# DigiIn1_1.net
KiCad netlist of a schematic drawn in EAGLE
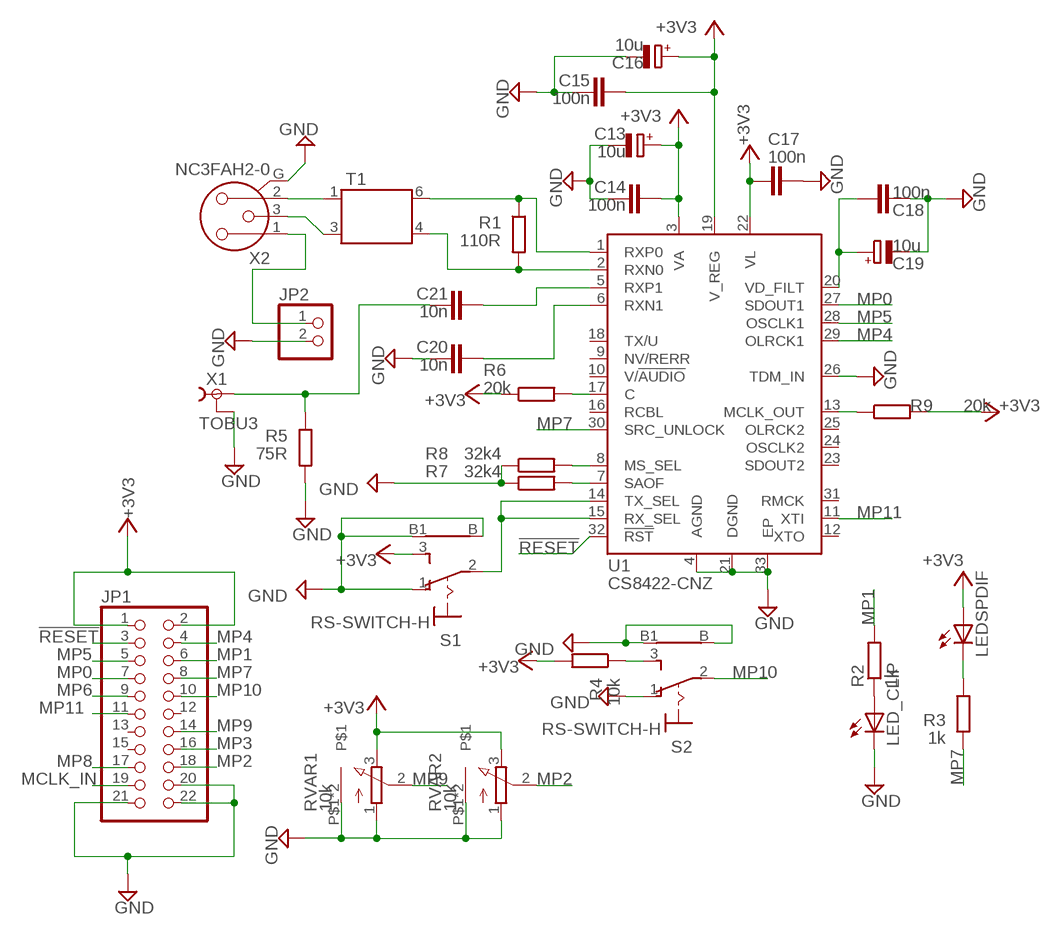
[diagram p0: schematic, sheet 1]

(export (version "E")
  (design (tool "Eeschema 10.0.6"))
  (components
    (comp (ref "C13")
      (value "10u")
      (footprint "eagle-import:E2-5")
      (libsource (lib "eagle-import") (part "CPOL-EUE2-5"))
    )
    (comp (ref "C14")
      (value "100n")
      (footprint "eagle-import:C025-024X044")
      (libsource (lib "eagle-import") (part "C-EU025-024X044"))
    )
    (comp (ref "C15")
      (value "100n")
      (footprint "eagle-import:C025-024X044")
      (libsource (lib "eagle-import") (part "C-EU025-024X044"))
    )
    (comp (ref "C16")
      (value "10u")
      (footprint "eagle-import:E2-5")
      (libsource (lib "eagle-import") (part "CPOL-EUE2-5"))
    )
    (comp (ref "C17")
      (value "100n")
      (footprint "eagle-import:C025-024X044")
      (libsource (lib "eagle-import") (part "C-EU025-024X044"))
    )
    (comp (ref "C18")
      (value "100n")
      (footprint "eagle-import:C025-024X044")
      (libsource (lib "eagle-import") (part "C-EU025-024X044"))
    )
    (comp (ref "C19")
      (value "10u")
      (footprint "eagle-import:E2-5")
      (libsource (lib "eagle-import") (part "CPOL-EUE2-5"))
    )
    (comp (ref "C20")
      (value "10n")
      (footprint "eagle-import:C075-032X103")
      (libsource (lib "eagle-import") (part "C-EU075-032X103"))
    )
    (comp (ref "C21")
      (value "10n")
      (footprint "eagle-import:C075-032X103")
      (libsource (lib "eagle-import") (part "C-EU075-032X103"))
    )
    (comp (ref "JP1")
      (value "PINHD-2X11")
      (footprint "eagle-import:2X11")
      (libsource (lib "eagle-import") (part "PINHD-2X11"))
    )
    (comp (ref "JP2")
      (value "PINHD-1X2")
      (footprint "eagle-import:1X02")
      (libsource (lib "eagle-import") (part "PINHD-1X2"))
    )
    (comp (ref "LEDSPDIF")
      (value "LED3MM")
      (footprint "eagle-import:LED3MM")
      (libsource (lib "eagle-import") (part "LED3MM"))
    )
    (comp (ref "LED_CLIP")
      (value "LED3MM")
      (footprint "eagle-import:LED3MM")
      (libsource (lib "eagle-import") (part "LED3MM"))
    )
    (comp (ref "R1")
      (value "110R")
      (footprint "eagle-import:0207_10")
      (libsource (lib "eagle-import") (part "R-EU_0207/10"))
    )
    (comp (ref "R2")
      (value "1k")
      (footprint "eagle-import:0207_10")
      (libsource (lib "eagle-import") (part "R-EU_0207/10"))
    )
    (comp (ref "R3")
      (value "1k")
      (footprint "eagle-import:0207_10")
      (libsource (lib "eagle-import") (part "R-EU_0207/10"))
    )
    (comp (ref "R4")
      (value "10k")
      (footprint "eagle-import:0207_10")
      (libsource (lib "eagle-import") (part "R-EU_0207/10"))
    )
    (comp (ref "R5")
      (value "75R")
      (footprint "eagle-import:0207_2V")
      (libsource (lib "eagle-import") (part "R-EU_0207/2V"))
    )
    (comp (ref "R6")
      (value "20k")
      (footprint "eagle-import:0207_10")
      (libsource (lib "eagle-import") (part "R-EU_0207/10"))
    )
    (comp (ref "R7")
      (value "32k4")
      (footprint "eagle-import:0207_10")
      (libsource (lib "eagle-import") (part "R-EU_0207/10"))
    )
    (comp (ref "R8")
      (value "32k4")
      (footprint "eagle-import:0207_10")
      (libsource (lib "eagle-import") (part "R-EU_0207/10"))
    )
    (comp (ref "R9")
      (value "20k")
      (footprint "eagle-import:0207_10")
      (libsource (lib "eagle-import") (part "R-EU_0207/10"))
    )
    (comp (ref "RVAR1")
      (value "10k")
      (footprint "eagle-import:ALPS-RK09")
      (libsource (lib "eagle-import") (part "ALPS-RK09"))
    )
    (comp (ref "RVAR2")
      (value "10k")
      (footprint "eagle-import:ALPS-RK09")
      (libsource (lib "eagle-import") (part "ALPS-RK09"))
    )
    (comp (ref "S1")
      (value "RS-SWITCH-H")
      (footprint "eagle-import:RS-SWITCH-H")
      (libsource (lib "eagle-import") (part "RS-SWITCH-H"))
    )
    (comp (ref "S2")
      (value "RS-SWITCH-H")
      (footprint "eagle-import:RS-SWITCH-H")
      (libsource (lib "eagle-import") (part "RS-SWITCH-H"))
    )
    (comp (ref "T1")
      (value "TRAFO_DIL6")
      (footprint "eagle-import:TRAFO_DIL6")
      (libsource (lib "eagle-import") (part "TRAFO_DIL6"))
    )
    (comp (ref "U1")
      (value "CS8422-CNZ")
      (footprint "eagle-import:QFN50P500X500X100-33N")
      (libsource (lib "eagle-import") (part "CS8422"))
    )
    (comp (ref "X1")
      (value "TOBU3")
      (footprint "eagle-import:TOBU3")
      (fields (field (name "MF") "FARNELL") (field (name "MPN") "TOBU 3"))
      (libsource (lib "eagle-import") (part "TOBU3"))
    )
    (comp (ref "X2")
      (value "NC3FAH2-0")
      (footprint "eagle-import:NC3FAH2-0")
      (fields (field (name "MPN") "NC3FAH-2-0"))
      (libsource (lib "eagle-import") (part "NC3FAH2-0"))
    )
  )
  (nets
    (net (code "1") (name "+3V3") (class "Default")
      (node (ref "C13") (pin "+") (pinfunction "+_+") (pintype "passive"))
      (node (ref "C14") (pin "1") (pinfunction "1_1") (pintype "passive"))
      (node (ref "C15") (pin "1") (pinfunction "1_1") (pintype "passive"))
      (node (ref "C16") (pin "+") (pinfunction "+_+") (pintype "passive"))
      (node (ref "C17") (pin "1") (pinfunction "1_1") (pintype "passive"))
      (node (ref "JP1") (pin "1") (pinfunction "1_1") (pintype "passive"))
      (node (ref "JP1") (pin "2") (pinfunction "2_2") (pintype "passive"))
      (node (ref "LEDSPDIF") (pin "A") (pinfunction "A_A") (pintype "passive"))
      (node (ref "R4") (pin "2") (pinfunction "2_2") (pintype "passive"))
      (node (ref "R6") (pin "1") (pinfunction "1_1") (pintype "passive"))
      (node (ref "R9") (pin "2") (pinfunction "2_2") (pintype "passive"))
      (node (ref "RVAR1") (pin "3") (pinfunction "3_3") (pintype "passive"))
      (node (ref "RVAR2") (pin "3") (pinfunction "3_3") (pintype "passive"))
      (node (ref "S1") (pin "3") (pinfunction "3_3") (pintype "passive"))
      (node (ref "U1") (pin "19") (pinfunction "V_REG_19") (pintype "bidirectional"))
      (node (ref "U1") (pin "22") (pinfunction "VL_22") (pintype "bidirectional"))
      (node (ref "U1") (pin "3") (pinfunction "VA_3") (pintype "bidirectional"))
    )
    (net (code "2") (name "/MCLK_IN") (class "Default")
      (node (ref "JP1") (pin "19") (pinfunction "19_19") (pintype "passive"))
    )
    (net (code "3") (name "/MP0") (class "Default")
      (node (ref "JP1") (pin "7") (pinfunction "7_7") (pintype "passive"))
      (node (ref "U1") (pin "27") (pinfunction "SDOUT1_27") (pintype "bidirectional"))
    )
    (net (code "4") (name "/MP1") (class "Default")
      (node (ref "JP1") (pin "6") (pinfunction "6_6") (pintype "passive"))
      (node (ref "R2") (pin "2") (pinfunction "2_2") (pintype "passive"))
    )
    (net (code "5") (name "/MP2") (class "Default")
      (node (ref "JP1") (pin "18") (pinfunction "18_18") (pintype "passive"))
      (node (ref "RVAR2") (pin "2") (pinfunction "2_2") (pintype "passive"))
    )
    (net (code "6") (name "/MP3") (class "Default")
      (node (ref "JP1") (pin "16") (pinfunction "16_16") (pintype "passive"))
    )
    (net (code "7") (name "/MP4") (class "Default")
      (node (ref "JP1") (pin "4") (pinfunction "4_4") (pintype "passive"))
      (node (ref "U1") (pin "29") (pinfunction "OLRCK1_29") (pintype "bidirectional"))
    )
    (net (code "8") (name "/MP5") (class "Default")
      (node (ref "JP1") (pin "5") (pinfunction "5_5") (pintype "passive"))
      (node (ref "U1") (pin "28") (pinfunction "OSCLK1_28") (pintype "bidirectional"))
    )
    (net (code "9") (name "/MP6") (class "Default")
      (node (ref "JP1") (pin "9") (pinfunction "9_9") (pintype "passive"))
    )
    (net (code "10") (name "/MP7") (class "Default")
      (node (ref "JP1") (pin "8") (pinfunction "8_8") (pintype "passive"))
      (node (ref "R3") (pin "1") (pinfunction "1_1") (pintype "passive"))
      (node (ref "U1") (pin "30") (pinfunction "SRC_UNLOCK_30") (pintype "bidirectional"))
    )
    (net (code "11") (name "/MP8") (class "Default")
      (node (ref "JP1") (pin "17") (pinfunction "17_17") (pintype "passive"))
    )
    (net (code "12") (name "/MP9") (class "Default")
      (node (ref "JP1") (pin "14") (pinfunction "14_14") (pintype "passive"))
      (node (ref "RVAR1") (pin "2") (pinfunction "2_2") (pintype "passive"))
    )
    (net (code "13") (name "/MP10") (class "Default")
      (node (ref "JP1") (pin "10") (pinfunction "10_10") (pintype "passive"))
      (node (ref "S2") (pin "2") (pinfunction "2_2") (pintype "passive"))
    )
    (net (code "14") (name "/MP11") (class "Default")
      (node (ref "JP1") (pin "11") (pinfunction "11_11") (pintype "passive"))
      (node (ref "U1") (pin "11") (pinfunction "XTI_11") (pintype "bidirectional"))
    )
    (net (code "15") (name "/~{RESET}") (class "Default")
      (node (ref "JP1") (pin "3") (pinfunction "3_3") (pintype "passive"))
      (node (ref "U1") (pin "32") (pinfunction "~{RST}_32") (pintype "bidirectional"))
    )
    (net (code "16") (name "GND") (class "Default")
      (node (ref "C13") (pin "-") (pinfunction "-_-") (pintype "passive"))
      (node (ref "C14") (pin "2") (pinfunction "2_2") (pintype "passive"))
      (node (ref "C15") (pin "2") (pinfunction "2_2") (pintype "passive"))
      (node (ref "C16") (pin "-") (pinfunction "-_-") (pintype "passive"))
      (node (ref "C17") (pin "2") (pinfunction "2_2") (pintype "passive"))
      (node (ref "C18") (pin "2") (pinfunction "2_2") (pintype "passive"))
      (node (ref "C19") (pin "-") (pinfunction "-_-") (pintype "passive"))
      (node (ref "C20") (pin "2") (pinfunction "2_2") (pintype "passive"))
      (node (ref "JP1") (pin "20") (pinfunction "20_20") (pintype "passive"))
      (node (ref "JP1") (pin "21") (pinfunction "21_21") (pintype "passive"))
      (node (ref "JP1") (pin "22") (pinfunction "22_22") (pintype "passive"))
      (node (ref "JP2") (pin "2") (pinfunction "2_2") (pintype "passive"))
      (node (ref "LED_CLIP") (pin "K") (pinfunction "C_K") (pintype "passive"))
      (node (ref "R5") (pin "2") (pinfunction "2_2") (pintype "passive"))
      (node (ref "R7") (pin "1") (pinfunction "1_1") (pintype "passive"))
      (node (ref "R8") (pin "1") (pinfunction "1_1") (pintype "passive"))
      (node (ref "RVAR1") (pin "1") (pinfunction "1_1") (pintype "passive"))
      (node (ref "RVAR1") (pin "P$1") (pinfunction "P$1_P$1") (pintype "bidirectional"))
      (node (ref "RVAR1") (pin "P$2") (pinfunction "P$1_P$2") (pintype "bidirectional"))
      (node (ref "RVAR2") (pin "1") (pinfunction "1_1") (pintype "passive"))
      (node (ref "RVAR2") (pin "P$1") (pinfunction "P$1_P$1") (pintype "bidirectional"))
      (node (ref "RVAR2") (pin "P$2") (pinfunction "P$1_P$2") (pintype "bidirectional"))
      (node (ref "S1") (pin "1") (pinfunction "1_1") (pintype "passive"))
      (node (ref "S1") (pin "B") (pinfunction "B_B") (pintype "passive"))
      (node (ref "S1") (pin "B1") (pinfunction "B1_B1") (pintype "passive"))
      (node (ref "S2") (pin "1") (pinfunction "1_1") (pintype "passive"))
      (node (ref "S2") (pin "B") (pinfunction "B_B") (pintype "passive"))
      (node (ref "S2") (pin "B1") (pinfunction "B1_B1") (pintype "passive"))
      (node (ref "U1") (pin "21") (pinfunction "DGND_21") (pintype "bidirectional"))
      (node (ref "U1") (pin "26") (pinfunction "TDM_IN_26") (pintype "bidirectional"))
      (node (ref "U1") (pin "33") (pinfunction "EP_33") (pintype "bidirectional"))
      (node (ref "U1") (pin "4") (pinfunction "AGND_4") (pintype "bidirectional"))
      (node (ref "X1") (pin "2") (pinfunction "2_2") (pintype "passive"))
      (node (ref "X1") (pin "2@1") (pinfunction "2_2@1") (pintype "passive"))
      (node (ref "X1") (pin "2@2") (pinfunction "2_2@2") (pintype "passive"))
      (node (ref "X2") (pin "G") (pinfunction "G_G") (pintype "passive"))
    )
    (net (code "17") (name "Net-(C21-Pad2)") (class "Default")
      (node (ref "C21") (pin "2") (pinfunction "2_2") (pintype "passive"))
      (node (ref "R5") (pin "1") (pinfunction "1_1") (pintype "passive"))
      (node (ref "X1") (pin "1") (pinfunction "1_1") (pintype "passive"))
    )
    (net (code "18") (name "Net-(JP2-Pad1)") (class "Default")
      (node (ref "JP2") (pin "1") (pinfunction "1_1") (pintype "passive"))
      (node (ref "X2") (pin "1") (pinfunction "1_1") (pintype "passive"))
    )
    (net (code "19") (name "Net-(LEDSPDIF-C)") (class "Default")
      (node (ref "LEDSPDIF") (pin "K") (pinfunction "C_K") (pintype "passive"))
      (node (ref "R3") (pin "2") (pinfunction "2_2") (pintype "passive"))
    )
    (net (code "20") (name "Net-(LED_CLIP-PadA)") (class "Default")
      (node (ref "LED_CLIP") (pin "A") (pinfunction "A_A") (pintype "passive"))
      (node (ref "R2") (pin "1") (pinfunction "1_1") (pintype "passive"))
    )
    (net (code "21") (name "Net-(R4-Pad1)") (class "Default")
      (node (ref "R4") (pin "1") (pinfunction "1_1") (pintype "passive"))
      (node (ref "S2") (pin "3") (pinfunction "3_3") (pintype "passive"))
    )
    (net (code "22") (name "Net-(T1-Pad1)") (class "Default")
      (node (ref "T1") (pin "1") (pinfunction "1_1") (pintype "passive"))
      (node (ref "X2") (pin "2") (pinfunction "2_2") (pintype "passive"))
    )
    (net (code "23") (name "Net-(T1-Pad3)") (class "Default")
      (node (ref "T1") (pin "3") (pinfunction "3_3") (pintype "passive"))
      (node (ref "X2") (pin "3") (pinfunction "3_3") (pintype "passive"))
    )
    (net (code "24") (name "Net-(U1-C)") (class "Default")
      (node (ref "R6") (pin "2") (pinfunction "2_2") (pintype "passive"))
      (node (ref "U1") (pin "17") (pinfunction "C_17") (pintype "bidirectional"))
    )
    (net (code "25") (name "Net-(U1-MCLK_OUT)") (class "Default")
      (node (ref "R9") (pin "1") (pinfunction "1_1") (pintype "passive"))
      (node (ref "U1") (pin "13") (pinfunction "MCLK_OUT_13") (pintype "bidirectional"))
    )
    (net (code "26") (name "Net-(U1-MS_SEL)") (class "Default")
      (node (ref "R8") (pin "2") (pinfunction "2_2") (pintype "passive"))
      (node (ref "U1") (pin "8") (pinfunction "MS_SEL_8") (pintype "bidirectional"))
    )
    (net (code "27") (name "Net-(U1-RXN0)") (class "Default")
      (node (ref "R1") (pin "2") (pinfunction "2_2") (pintype "passive"))
      (node (ref "T1") (pin "4") (pinfunction "4_4") (pintype "passive"))
      (node (ref "U1") (pin "2") (pinfunction "RXN0_2") (pintype "bidirectional"))
    )
    (net (code "28") (name "Net-(U1-RXN1)") (class "Default")
      (node (ref "C20") (pin "1") (pinfunction "1_1") (pintype "passive"))
      (node (ref "U1") (pin "6") (pinfunction "RXN1_6") (pintype "bidirectional"))
    )
    (net (code "29") (name "Net-(U1-RXP0)") (class "Default")
      (node (ref "R1") (pin "1") (pinfunction "1_1") (pintype "passive"))
      (node (ref "T1") (pin "6") (pinfunction "6_6") (pintype "passive"))
      (node (ref "U1") (pin "1") (pinfunction "RXP0_1") (pintype "bidirectional"))
    )
    (net (code "30") (name "Net-(U1-RXP1)") (class "Default")
      (node (ref "C21") (pin "1") (pinfunction "1_1") (pintype "passive"))
      (node (ref "U1") (pin "5") (pinfunction "RXP1_5") (pintype "bidirectional"))
    )
    (net (code "31") (name "Net-(U1-RX_SEL)") (class "Default")
      (node (ref "S1") (pin "2") (pinfunction "2_2") (pintype "passive"))
      (node (ref "U1") (pin "14") (pinfunction "TX_SEL_14") (pintype "bidirectional"))
      (node (ref "U1") (pin "15") (pinfunction "RX_SEL_15") (pintype "bidirectional"))
    )
    (net (code "32") (name "Net-(U1-SAOF)") (class "Default")
      (node (ref "R7") (pin "2") (pinfunction "2_2") (pintype "passive"))
      (node (ref "U1") (pin "7") (pinfunction "SAOF_7") (pintype "bidirectional"))
    )
    (net (code "33") (name "Net-(U1-VD_FILT)") (class "Default")
      (node (ref "C18") (pin "1") (pinfunction "1_1") (pintype "passive"))
      (node (ref "C19") (pin "+") (pinfunction "+_+") (pintype "passive"))
      (node (ref "U1") (pin "20") (pinfunction "VD_FILT_20") (pintype "bidirectional"))
    )
    (net (code "34") (name "unconnected-(JP1-Pad12)") (class "Default")
      (node (ref "JP1") (pin "12") (pinfunction "12_12") (pintype "passive"))
    )
    (net (code "35") (name "unconnected-(JP1-Pad13)") (class "Default")
      (node (ref "JP1") (pin "13") (pinfunction "13_13") (pintype "passive"))
    )
    (net (code "36") (name "unconnected-(JP1-Pad15)") (class "Default")
      (node (ref "JP1") (pin "15") (pinfunction "15_15") (pintype "passive"))
    )
    (net (code "37") (name "unconnected-(U1-NV{slash}RERR-Pad9)") (class "Default")
      (node (ref "U1") (pin "9") (pinfunction "NV/RERR_9") (pintype "bidirectional"))
    )
    (net (code "38") (name "unconnected-(U1-OLRCK2-Pad25)") (class "Default")
      (node (ref "U1") (pin "25") (pinfunction "OLRCK2_25") (pintype "bidirectional"))
    )
    (net (code "39") (name "unconnected-(U1-OSCLK2-Pad24)") (class "Default")
      (node (ref "U1") (pin "24") (pinfunction "OSCLK2_24") (pintype "bidirectional"))
    )
    (net (code "40") (name "unconnected-(U1-RCBL-Pad16)") (class "Default")
      (node (ref "U1") (pin "16") (pinfunction "RCBL_16") (pintype "bidirectional"))
    )
    (net (code "41") (name "unconnected-(U1-RMCK-Pad31)") (class "Default")
      (node (ref "U1") (pin "31") (pinfunction "RMCK_31") (pintype "bidirectional"))
    )
    (net (code "42") (name "unconnected-(U1-SDOUT2-Pad23)") (class "Default")
      (node (ref "U1") (pin "23") (pinfunction "SDOUT2_23") (pintype "bidirectional"))
    )
    (net (code "43") (name "unconnected-(U1-TX{slash}U-Pad18)") (class "Default")
      (node (ref "U1") (pin "18") (pinfunction "TX/U_18") (pintype "bidirectional"))
    )
    (net (code "44") (name "unconnected-(U1-V{slash}~{AUDIO}-Pad10)") (class "Default")
      (node (ref "U1") (pin "10") (pinfunction "V/~{AUDIO}_10") (pintype "bidirectional"))
    )
    (net (code "45") (name "unconnected-(U1-XTO-Pad12)") (class "Default")
      (node (ref "U1") (pin "12") (pinfunction "XTO_12") (pintype "bidirectional"))
    )
  )
)
